# Welduino.net
KiCad netlist of a schematic drawn in EAGLE
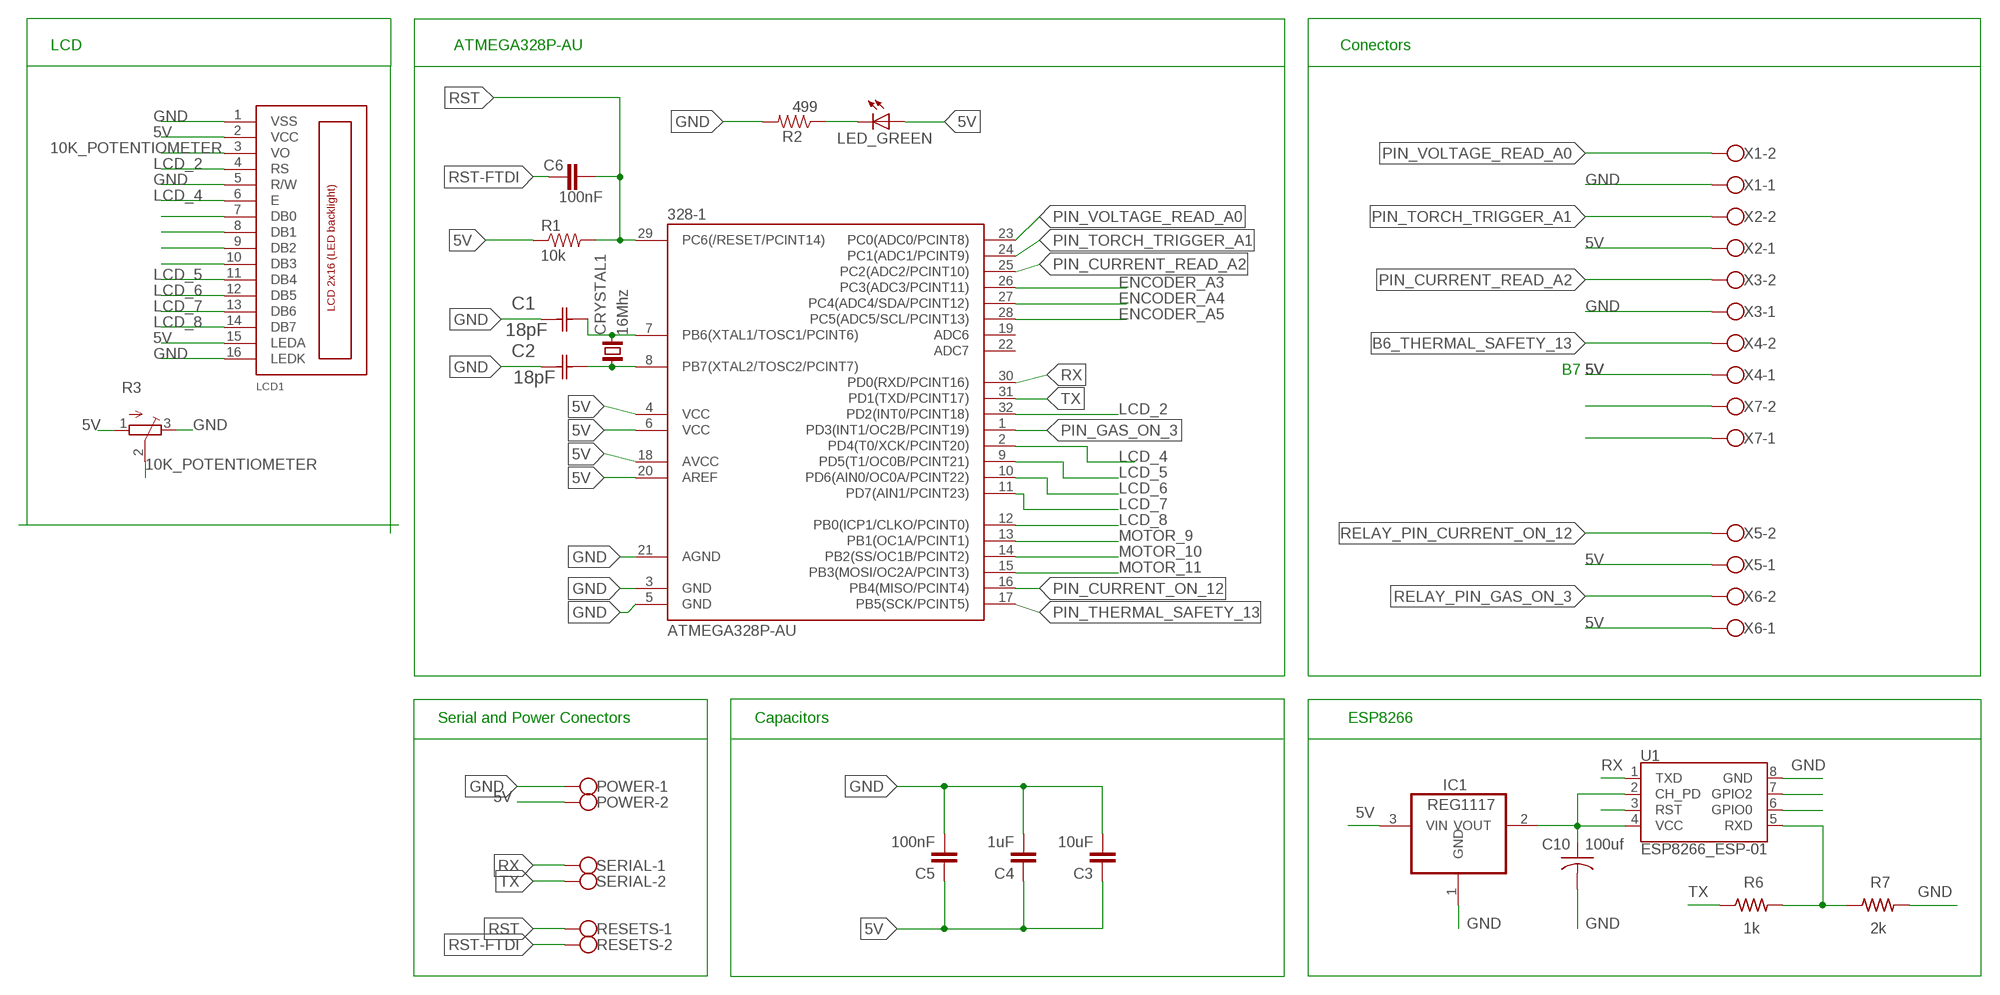
[diagram p0: schematic, sheet 1]

(export (version "E")
  (design (tool "Eeschema 10.0.6"))
  (components
    (comp (ref "328-1")
      (value "ATMEGA328P-AU")
      (footprint "eagle-import:TQFP32-08")
      (libsource (lib "eagle-import") (part "ATMEGA48/88/168-AU"))
    )
    (comp (ref "C1")
      (value "18pF")
      (footprint "eagle-import:CAPC3216X178N")
      (fields (field (name "MPN") "0612ZC225MAT2A") (field (name "TOLERANCE") "±20%"))
      (libsource (lib "eagle-import") (part "0612ZC225MAT2A"))
    )
    (comp (ref "C2")
      (value "18pF")
      (footprint "eagle-import:CAPC3216X178N")
      (fields (field (name "MPN") "0612ZC225MAT2A") (field (name "TOLERANCE") "±20%"))
      (libsource (lib "eagle-import") (part "0612ZC225MAT2A"))
    )
    (comp (ref "C3")
      (value "10uF")
      (footprint "eagle-import:1206")
      (libsource (lib "eagle-import") (part "CAP1206"))
    )
    (comp (ref "C4")
      (value "1uF")
      (footprint "eagle-import:1206")
      (libsource (lib "eagle-import") (part "CAP1206"))
    )
    (comp (ref "C5")
      (value "100nF")
      (footprint "eagle-import:1206")
      (libsource (lib "eagle-import") (part "CAP1206"))
    )
    (comp (ref "C6")
      (value "100nF")
      (footprint "eagle-import:1206")
      (libsource (lib "eagle-import") (part "CAP1206"))
    )
    (comp (ref "C10")
      (value "100uf")
      (footprint "eagle-import:C1206FAB")
      (libsource (lib "eagle-import") (part "CAP-US1206FAB"))
    )
    (comp (ref "CRYSTAL1")
      (value "16Mhz")
      (footprint "eagle-import:2-SMD-5X3")
      (fields (field (name "MF") "NDK America,") (field (name "MP") "NX5032GA"))
      (libsource (lib "eagle-import") (part "NX5032GA"))
    )
    (comp (ref "IC1")
      (value "REG1117")
      (footprint "eagle-import:SOT223")
      (libsource (lib "eagle-import") (part "REG1117"))
    )
    (comp (ref "LCD1")
      (value "LCD_2X16_SIL")
      (footprint "eagle-import:HY-1602F")
      (libsource (lib "eagle-import") (part "LCD_2X16_SIL"))
    )
    (comp (ref "LED_GREEN")
      (value "LED1206")
      (footprint "eagle-import:1206")
      (libsource (lib "eagle-import") (part "LED1206"))
    )
    (comp (ref "POWER")
      (value "W237-102")
      (footprint "eagle-import:W237-102")
      (fields (field (name "MPN") "237-102"))
      (libsource (lib "eagle-import") (part "W237-102"))
    )
    (comp (ref "R1")
      (value "10k")
      (footprint "eagle-import:1206")
      (libsource (lib "eagle-import") (part "RESISTOR1206"))
    )
    (comp (ref "R2")
      (value "499")
      (footprint "eagle-import:1206")
      (libsource (lib "eagle-import") (part "RESISTOR1206"))
    )
    (comp (ref "R3")
      (value "TRIM_EU-3223J")
      (footprint "eagle-import:3223J")
      (libsource (lib "eagle-import") (part "TRIM_EU-3223J"))
    )
    (comp (ref "R6")
      (value "1k")
      (footprint "eagle-import:R1206FAB")
      (libsource (lib "eagle-import") (part "RES-US1206FAB"))
    )
    (comp (ref "R7")
      (value "2k")
      (footprint "eagle-import:R1206FAB")
      (libsource (lib "eagle-import") (part "RES-US1206FAB"))
    )
    (comp (ref "RESETS")
      (value "W237-102")
      (footprint "eagle-import:W237-102")
      (fields (field (name "MPN") "237-102"))
      (libsource (lib "eagle-import") (part "W237-102"))
    )
    (comp (ref "SERIAL")
      (value "W237-102")
      (footprint "eagle-import:W237-102")
      (fields (field (name "MPN") "237-102"))
      (libsource (lib "eagle-import") (part "W237-102"))
    )
    (comp (ref "U1")
      (value "ESP8266_ESP-01")
      (footprint "eagle-import:ESP8266_ESP-01")
      (libsource (lib "eagle-import") (part "ESP8266_ESP-01"))
    )
    (comp (ref "X1")
      (value "W237-102")
      (footprint "eagle-import:W237-102")
      (fields (field (name "MPN") "237-102"))
      (libsource (lib "eagle-import") (part "W237-102"))
    )
    (comp (ref "X2")
      (value "W237-102")
      (footprint "eagle-import:W237-102")
      (fields (field (name "MPN") "237-102"))
      (libsource (lib "eagle-import") (part "W237-102"))
    )
    (comp (ref "X3")
      (value "W237-102")
      (footprint "eagle-import:W237-102")
      (fields (field (name "MPN") "237-102"))
      (libsource (lib "eagle-import") (part "W237-102"))
    )
    (comp (ref "X4")
      (value "W237-102")
      (footprint "eagle-import:W237-102")
      (fields (field (name "MPN") "237-102"))
      (libsource (lib "eagle-import") (part "W237-102"))
    )
    (comp (ref "X5")
      (value "W237-102")
      (footprint "eagle-import:W237-102")
      (fields (field (name "MPN") "237-102"))
      (libsource (lib "eagle-import") (part "W237-102"))
    )
    (comp (ref "X6")
      (value "W237-102")
      (footprint "eagle-import:W237-102")
      (fields (field (name "MPN") "237-102"))
      (libsource (lib "eagle-import") (part "W237-102"))
    )
    (comp (ref "X7")
      (value "W237-102")
      (footprint "eagle-import:W237-102")
      (fields (field (name "MPN") "237-102"))
      (libsource (lib "eagle-import") (part "W237-102"))
    )
  )
  (nets
    (net (code "1") (name "5V") (class "Default")
      (node (ref "328-1") (pin "18") (pinfunction "AVCC_18") (pintype "passive"))
      (node (ref "328-1") (pin "20") (pinfunction "AREF_20") (pintype "passive"))
      (node (ref "328-1") (pin "4") (pinfunction "VCC_4") (pintype "power_in"))
      (node (ref "328-1") (pin "6") (pinfunction "VCC_6") (pintype "power_in"))
      (node (ref "C3") (pin "1") (pinfunction "1_1") (pintype "passive"))
      (node (ref "C4") (pin "1") (pinfunction "1_1") (pintype "passive"))
      (node (ref "C5") (pin "1") (pinfunction "1_1") (pintype "passive"))
      (node (ref "IC1") (pin "3") (pinfunction "VIN_3") (pintype "input"))
      (node (ref "LCD1") (pin "15") (pinfunction "LEDA_15") (pintype "passive"))
      (node (ref "LCD1") (pin "2") (pinfunction "VCC_2") (pintype "power_in"))
      (node (ref "LED_GREEN") (pin "1") (pinfunction "A_1") (pintype "passive"))
      (node (ref "POWER") (pin "2") (pinfunction "KL_2") (pintype "passive"))
      (node (ref "R1") (pin "1") (pinfunction "1_1") (pintype "passive"))
      (node (ref "R3") (pin "1") (pinfunction "A_1") (pintype "passive"))
      (node (ref "X2") (pin "1") (pinfunction "KL_1") (pintype "passive"))
      (node (ref "X4") (pin "1") (pinfunction "KL_1") (pintype "passive"))
      (node (ref "X5") (pin "1") (pinfunction "KL_1") (pintype "passive"))
      (node (ref "X6") (pin "1") (pinfunction "KL_1") (pintype "passive"))
    )
    (net (code "2") (name "10K_POTENTIOMETER") (class "Default")
      (node (ref "LCD1") (pin "3") (pinfunction "VO_3") (pintype "input"))
      (node (ref "R3") (pin "2") (pinfunction "S_2") (pintype "passive"))
    )
    (net (code "3") (name "B6_THERMAL_SAFETY_13") (class "Default")
      (node (ref "X4") (pin "2") (pinfunction "KL_2") (pintype "passive"))
    )
    (net (code "4") (name "ENCODER_A3") (class "Default")
      (node (ref "328-1") (pin "26") (pinfunction "PC3(ADC3/PCINT11)_26") (pintype "bidirectional"))
    )
    (net (code "5") (name "ENCODER_A4") (class "Default")
      (node (ref "328-1") (pin "27") (pinfunction "PC4(ADC4/SDA/PCINT12)_27") (pintype "bidirectional"))
    )
    (net (code "6") (name "ENCODER_A5") (class "Default")
      (node (ref "328-1") (pin "28") (pinfunction "PC5(ADC5/SCL/PCINT13)_28") (pintype "bidirectional"))
    )
    (net (code "7") (name "GND") (class "Default")
      (node (ref "328-1") (pin "21") (pinfunction "AGND_21") (pintype "power_in"))
      (node (ref "328-1") (pin "3") (pinfunction "GND_3") (pintype "power_in"))
      (node (ref "328-1") (pin "5") (pinfunction "GND_5") (pintype "power_in"))
      (node (ref "C1") (pin "1") (pinfunction "C1_1") (pintype "passive"))
      (node (ref "C10") (pin "2") (pinfunction "2_2") (pintype "passive"))
      (node (ref "C2") (pin "1") (pinfunction "C1_1") (pintype "passive"))
      (node (ref "C3") (pin "2") (pinfunction "2_2") (pintype "passive"))
      (node (ref "C4") (pin "2") (pinfunction "2_2") (pintype "passive"))
      (node (ref "C5") (pin "2") (pinfunction "2_2") (pintype "passive"))
      (node (ref "IC1") (pin "1") (pinfunction "GND_1") (pintype "power_in"))
      (node (ref "LCD1") (pin "1") (pinfunction "VSS_1") (pintype "power_in"))
      (node (ref "LCD1") (pin "16") (pinfunction "LEDK_16") (pintype "passive"))
      (node (ref "LCD1") (pin "5") (pinfunction "R/W_5") (pintype "input"))
      (node (ref "POWER") (pin "1") (pinfunction "KL_1") (pintype "passive"))
      (node (ref "R2") (pin "2") (pinfunction "2_2") (pintype "passive"))
      (node (ref "R3") (pin "3") (pinfunction "E_3") (pintype "passive"))
      (node (ref "R7") (pin "2") (pinfunction "2_2") (pintype "passive"))
      (node (ref "U1") (pin "8") (pinfunction "GND_8") (pintype "bidirectional"))
      (node (ref "X1") (pin "1") (pinfunction "KL_1") (pintype "passive"))
      (node (ref "X3") (pin "1") (pinfunction "KL_1") (pintype "passive"))
    )
    (net (code "8") (name "LCD_2") (class "Default")
      (node (ref "328-1") (pin "32") (pinfunction "PD2(INT0/PCINT18)_32") (pintype "bidirectional"))
      (node (ref "LCD1") (pin "4") (pinfunction "RS_4") (pintype "input"))
    )
    (net (code "9") (name "LCD_4") (class "Default")
      (node (ref "328-1") (pin "2") (pinfunction "PD4(T0/XCK/PCINT20)_2") (pintype "bidirectional"))
      (node (ref "LCD1") (pin "6") (pinfunction "E_6") (pintype "input"))
    )
    (net (code "10") (name "LCD_5") (class "Default")
      (node (ref "328-1") (pin "9") (pinfunction "PD5(T1/OC0B/PCINT21)_9") (pintype "bidirectional"))
      (node (ref "LCD1") (pin "11") (pinfunction "DB4_11") (pintype "bidirectional"))
    )
    (net (code "11") (name "LCD_6") (class "Default")
      (node (ref "328-1") (pin "10") (pinfunction "PD6(AIN0/OC0A/PCINT22)_10") (pintype "bidirectional"))
      (node (ref "LCD1") (pin "12") (pinfunction "DB5_12") (pintype "bidirectional"))
    )
    (net (code "12") (name "LCD_7") (class "Default")
      (node (ref "328-1") (pin "11") (pinfunction "PD7(AIN1/PCINT23)_11") (pintype "bidirectional"))
      (node (ref "LCD1") (pin "13") (pinfunction "DB6_13") (pintype "bidirectional"))
    )
    (net (code "13") (name "LCD_8") (class "Default")
      (node (ref "328-1") (pin "12") (pinfunction "PB0(ICP1/CLKO/PCINT0)_12") (pintype "bidirectional"))
      (node (ref "LCD1") (pin "14") (pinfunction "DB7_14") (pintype "bidirectional"))
    )
    (net (code "14") (name "MOTOR_9") (class "Default")
      (node (ref "328-1") (pin "13") (pinfunction "PB1(OC1A/PCINT1)_13") (pintype "bidirectional"))
    )
    (net (code "15") (name "MOTOR_10") (class "Default")
      (node (ref "328-1") (pin "14") (pinfunction "PB2(SS/OC1B/PCINT2)_14") (pintype "bidirectional"))
    )
    (net (code "16") (name "MOTOR_11") (class "Default")
      (node (ref "328-1") (pin "15") (pinfunction "PB3(MOSI/OC2A/PCINT3)_15") (pintype "bidirectional"))
    )
    (net (code "17") (name "Net-(328-1-PB6(XTAL1{slash}TOSC1{slash}PCINT6))") (class "Default")
      (node (ref "328-1") (pin "7") (pinfunction "PB6(XTAL1/TOSC1/PCINT6)_7") (pintype "bidirectional"))
      (node (ref "C1") (pin "2") (pinfunction "C2_2") (pintype "passive"))
      (node (ref "CRYSTAL1") (pin "2") (pinfunction "2_2") (pintype "passive"))
    )
    (net (code "18") (name "Net-(328-1-PB7(XTAL2{slash}TOSC2{slash}PCINT7))") (class "Default")
      (node (ref "328-1") (pin "8") (pinfunction "PB7(XTAL2/TOSC2/PCINT7)_8") (pintype "bidirectional"))
      (node (ref "C2") (pin "2") (pinfunction "C2_2") (pintype "passive"))
      (node (ref "CRYSTAL1") (pin "1") (pinfunction "1_1") (pintype "passive"))
    )
    (net (code "19") (name "Net-(IC1-VOUT)") (class "Default")
      (node (ref "C10") (pin "1") (pinfunction "1_1") (pintype "passive"))
      (node (ref "IC1") (pin "2") (pinfunction "VOUT_2") (pintype "output"))
      (node (ref "U1") (pin "2") (pinfunction "CH_PD_2") (pintype "bidirectional"))
      (node (ref "U1") (pin "4") (pinfunction "VCC_4") (pintype "bidirectional"))
    )
    (net (code "20") (name "Net-(LED_GREEN-C)") (class "Default")
      (node (ref "LED_GREEN") (pin "2") (pinfunction "C_2") (pintype "passive"))
      (node (ref "R2") (pin "1") (pinfunction "1_1") (pintype "passive"))
    )
    (net (code "21") (name "Net-(U1-RXD)") (class "Default")
      (node (ref "R6") (pin "2") (pinfunction "2_2") (pintype "passive"))
      (node (ref "R7") (pin "1") (pinfunction "1_1") (pintype "passive"))
      (node (ref "U1") (pin "5") (pinfunction "RXD_5") (pintype "bidirectional"))
    )
    (net (code "22") (name "PIN_CURRENT_ON_12") (class "Default")
      (node (ref "328-1") (pin "16") (pinfunction "PB4(MISO/PCINT4)_16") (pintype "bidirectional"))
    )
    (net (code "23") (name "PIN_CURRENT_READ_A2") (class "Default")
      (node (ref "328-1") (pin "25") (pinfunction "PC2(ADC2/PCINT10)_25") (pintype "bidirectional"))
      (node (ref "X3") (pin "2") (pinfunction "KL_2") (pintype "passive"))
    )
    (net (code "24") (name "PIN_GAS_ON_3") (class "Default")
      (node (ref "328-1") (pin "1") (pinfunction "PD3(INT1/OC2B/PCINT19)_1") (pintype "bidirectional"))
    )
    (net (code "25") (name "PIN_THERMAL_SAFETY_13") (class "Default")
      (node (ref "328-1") (pin "17") (pinfunction "PB5(SCK/PCINT5)_17") (pintype "bidirectional"))
    )
    (net (code "26") (name "PIN_TORCH_TRIGGER_A1") (class "Default")
      (node (ref "328-1") (pin "24") (pinfunction "PC1(ADC1/PCINT9)_24") (pintype "bidirectional"))
      (node (ref "X2") (pin "2") (pinfunction "KL_2") (pintype "passive"))
    )
    (net (code "27") (name "PIN_VOLTAGE_READ_A0") (class "Default")
      (node (ref "328-1") (pin "23") (pinfunction "PC0(ADC0/PCINT8)_23") (pintype "bidirectional"))
      (node (ref "X1") (pin "2") (pinfunction "KL_2") (pintype "passive"))
    )
    (net (code "28") (name "RELAY_PIN_CURRENT_ON_12") (class "Default")
      (node (ref "X5") (pin "2") (pinfunction "KL_2") (pintype "passive"))
    )
    (net (code "29") (name "RELAY_PIN_GAS_ON_3") (class "Default")
      (node (ref "X6") (pin "2") (pinfunction "KL_2") (pintype "passive"))
    )
    (net (code "30") (name "RST") (class "Default")
      (node (ref "328-1") (pin "29") (pinfunction "PC6(/RESET/PCINT14)_29") (pintype "bidirectional"))
      (node (ref "C6") (pin "1") (pinfunction "1_1") (pintype "passive"))
      (node (ref "R1") (pin "2") (pinfunction "2_2") (pintype "passive"))
      (node (ref "RESETS") (pin "1") (pinfunction "KL_1") (pintype "passive"))
    )
    (net (code "31") (name "RST-FTDI") (class "Default")
      (node (ref "C6") (pin "2") (pinfunction "2_2") (pintype "passive"))
      (node (ref "RESETS") (pin "2") (pinfunction "KL_2") (pintype "passive"))
    )
    (net (code "32") (name "RX") (class "Default")
      (node (ref "328-1") (pin "30") (pinfunction "PD0(RXD/PCINT16)_30") (pintype "bidirectional"))
      (node (ref "SERIAL") (pin "1") (pinfunction "KL_1") (pintype "passive"))
      (node (ref "U1") (pin "1") (pinfunction "TXD_1") (pintype "bidirectional"))
    )
    (net (code "33") (name "TX") (class "Default")
      (node (ref "328-1") (pin "31") (pinfunction "PD1(TXD/PCINT17)_31") (pintype "bidirectional"))
      (node (ref "R6") (pin "1") (pinfunction "1_1") (pintype "passive"))
      (node (ref "SERIAL") (pin "2") (pinfunction "KL_2") (pintype "passive"))
    )
    (net (code "34") (name "unconnected-(328-1-ADC6-Pad19)") (class "Default")
      (node (ref "328-1") (pin "19") (pinfunction "ADC6_19") (pintype "passive"))
    )
    (net (code "35") (name "unconnected-(328-1-ADC7-Pad22)") (class "Default")
      (node (ref "328-1") (pin "22") (pinfunction "ADC7_22") (pintype "passive"))
    )
    (net (code "36") (name "unconnected-(LCD1-DB0-Pad7)") (class "Default")
      (node (ref "LCD1") (pin "7") (pinfunction "DB0_7") (pintype "bidirectional"))
    )
    (net (code "37") (name "unconnected-(LCD1-DB1-Pad8)") (class "Default")
      (node (ref "LCD1") (pin "8") (pinfunction "DB1_8") (pintype "bidirectional"))
    )
    (net (code "38") (name "unconnected-(LCD1-DB2-Pad9)") (class "Default")
      (node (ref "LCD1") (pin "9") (pinfunction "DB2_9") (pintype "bidirectional"))
    )
    (net (code "39") (name "unconnected-(LCD1-DB3-Pad10)") (class "Default")
      (node (ref "LCD1") (pin "10") (pinfunction "DB3_10") (pintype "bidirectional"))
    )
    (net (code "40") (name "unconnected-(U1-GPIO0-Pad6)") (class "Default")
      (node (ref "U1") (pin "6") (pinfunction "GPIO0_6") (pintype "bidirectional"))
    )
    (net (code "41") (name "unconnected-(U1-GPIO2-Pad7)") (class "Default")
      (node (ref "U1") (pin "7") (pinfunction "GPIO2_7") (pintype "bidirectional"))
    )
    (net (code "42") (name "unconnected-(U1-RST-Pad3)") (class "Default")
      (node (ref "U1") (pin "3") (pinfunction "RST_3") (pintype "bidirectional"))
    )
    (net (code "43") (name "unconnected-(X7A-KL-Pad1)") (class "Default")
      (node (ref "X7") (pin "1") (pinfunction "KL_1") (pintype "passive"))
    )
    (net (code "44") (name "unconnected-(X7B-KL-Pad2)") (class "Default")
      (node (ref "X7") (pin "2") (pinfunction "KL_2") (pintype "passive"))
    )
  )
)
